# Add-OnV5.net
KiCad netlist of a schematic drawn in EAGLE
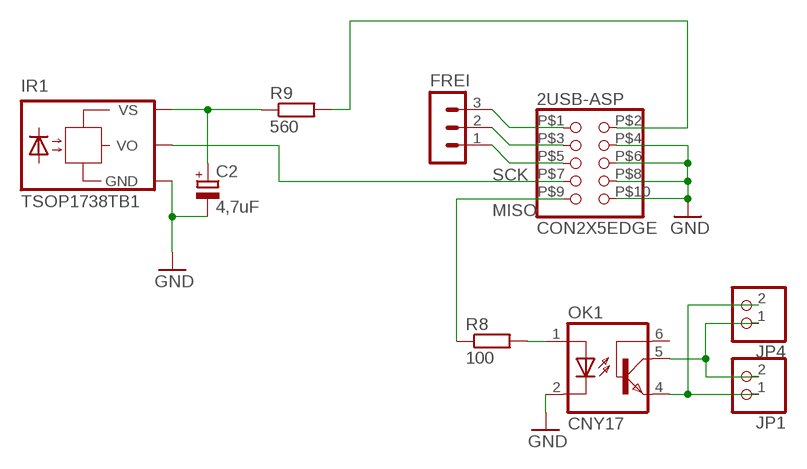
[diagram p0: schematic, sheet 1]

(export (version "E")
  (design (tool "Eeschema 10.0.6"))
  (components
    (comp (ref "2USB-ASP")
      (value "CON2X5EDGE")
      (footprint "eagle-import:CON2X5EDGE")
      (libsource (lib "eagle-import") (part "CON2X5EDGE"))
    )
    (comp (ref "C2")
      (value "4,7uF")
      (footprint "eagle-import:E1,8-4")
      (libsource (lib "eagle-import") (part "CPOL-EUE1.8-4"))
    )
    (comp (ref "FREI")
      (value "MA03-1")
      (footprint "eagle-import:MA03-1")
      (libsource (lib "eagle-import") (part "MA03-1"))
    )
    (comp (ref "IR1")
      (value "TSOP1738TB1")
      (footprint "eagle-import:TSOP17_TB1")
      (libsource (lib "eagle-import") (part "TSOP17TB138"))
    )
    (comp (ref "JP1")
      (value "PINHD-1X2")
      (footprint "eagle-import:1X02")
      (libsource (lib "eagle-import") (part "PINHD-1X2"))
    )
    (comp (ref "JP4")
      (value "PINHD-1X2")
      (footprint "eagle-import:1X02")
      (libsource (lib "eagle-import") (part "PINHD-1X2"))
    )
    (comp (ref "OK1")
      (value "CNY17")
      (footprint "eagle-import:DIL06")
      (fields (field (name "MPN") "CNY17-1"))
      (libsource (lib "eagle-import") (part "CNY17"))
    )
    (comp (ref "R8")
      (value "100")
      (footprint "eagle-import:0204_7")
      (libsource (lib "eagle-import") (part "R-EU_0204/7"))
    )
    (comp (ref "R9")
      (value "560")
      (footprint "eagle-import:0204_7")
      (libsource (lib "eagle-import") (part "R-EU_0204/7"))
    )
  )
  (nets
    (net (code "1") (name "/MISO") (class "Default")
      (node (ref "2USB-ASP") (pin "P$9") (pinfunction "9_P$9") (pintype "passive"))
      (node (ref "R8") (pin "1") (pinfunction "1_1") (pintype "passive"))
    )
    (net (code "2") (name "/SCK") (class "Default")
      (node (ref "2USB-ASP") (pin "P$7") (pinfunction "7_P$7") (pintype "passive"))
      (node (ref "IR1") (pin "VO") (pinfunction "VO_VO") (pintype "open_collector"))
    )
    (net (code "3") (name "GND") (class "Default")
      (node (ref "2USB-ASP") (pin "P$10") (pinfunction "10_P$10") (pintype "passive"))
      (node (ref "2USB-ASP") (pin "P$4") (pinfunction "4_P$4") (pintype "passive"))
      (node (ref "2USB-ASP") (pin "P$6") (pinfunction "6_P$6") (pintype "passive"))
      (node (ref "2USB-ASP") (pin "P$8") (pinfunction "8_P$8") (pintype "passive"))
      (node (ref "C2") (pin "-") (pinfunction "-_-") (pintype "passive"))
      (node (ref "IR1") (pin "GND") (pinfunction "GND_GND") (pintype "power_in"))
      (node (ref "OK1") (pin "2") (pinfunction "C_2") (pintype "passive"))
    )
    (net (code "4") (name "Net-(2USB-ASP-1)") (class "Default")
      (node (ref "2USB-ASP") (pin "P$1") (pinfunction "1_P$1") (pintype "passive"))
      (node (ref "FREI") (pin "3") (pinfunction "3_3") (pintype "passive"))
    )
    (net (code "5") (name "Net-(2USB-ASP-2)") (class "Default")
      (node (ref "2USB-ASP") (pin "P$2") (pinfunction "2_P$2") (pintype "passive"))
      (node (ref "R9") (pin "2") (pinfunction "2_2") (pintype "passive"))
    )
    (net (code "6") (name "Net-(2USB-ASP-3)") (class "Default")
      (node (ref "2USB-ASP") (pin "P$3") (pinfunction "3_P$3") (pintype "passive"))
      (node (ref "FREI") (pin "2") (pinfunction "2_2") (pintype "passive"))
    )
    (net (code "7") (name "Net-(2USB-ASP-5)") (class "Default")
      (node (ref "2USB-ASP") (pin "P$5") (pinfunction "5_P$5") (pintype "passive"))
      (node (ref "FREI") (pin "1") (pinfunction "1_1") (pintype "passive"))
    )
    (net (code "8") (name "Net-(C2-Pad+)") (class "Default")
      (node (ref "C2") (pin "+") (pinfunction "+_+") (pintype "passive"))
      (node (ref "IR1") (pin "VS") (pinfunction "VS_VS") (pintype "power_in"))
      (node (ref "R9") (pin "1") (pinfunction "1_1") (pintype "passive"))
    )
    (net (code "9") (name "Net-(OK1-A)") (class "Default")
      (node (ref "OK1") (pin "1") (pinfunction "A_1") (pintype "passive"))
      (node (ref "R8") (pin "2") (pinfunction "2_2") (pintype "passive"))
    )
    (net (code "10") (name "Net-(OK1-COL)") (class "Default")
      (node (ref "JP1") (pin "2") (pinfunction "2_2") (pintype "passive"))
      (node (ref "JP4") (pin "1") (pinfunction "1_1") (pintype "passive"))
      (node (ref "OK1") (pin "5") (pinfunction "COL_5") (pintype "passive"))
    )
    (net (code "11") (name "Net-(OK1-EMI)") (class "Default")
      (node (ref "JP1") (pin "1") (pinfunction "1_1") (pintype "passive"))
      (node (ref "JP4") (pin "2") (pinfunction "2_2") (pintype "passive"))
      (node (ref "OK1") (pin "4") (pinfunction "EMI_4") (pintype "passive"))
    )
    (net (code "12") (name "unconnected-(OK1-BAS-Pad6)") (class "Default")
      (node (ref "OK1") (pin "6") (pinfunction "BAS_6") (pintype "passive"))
    )
  )
)
